# CD_Power_supply.net
KiCad netlist of a schematic drawn in EasyEDA Pro
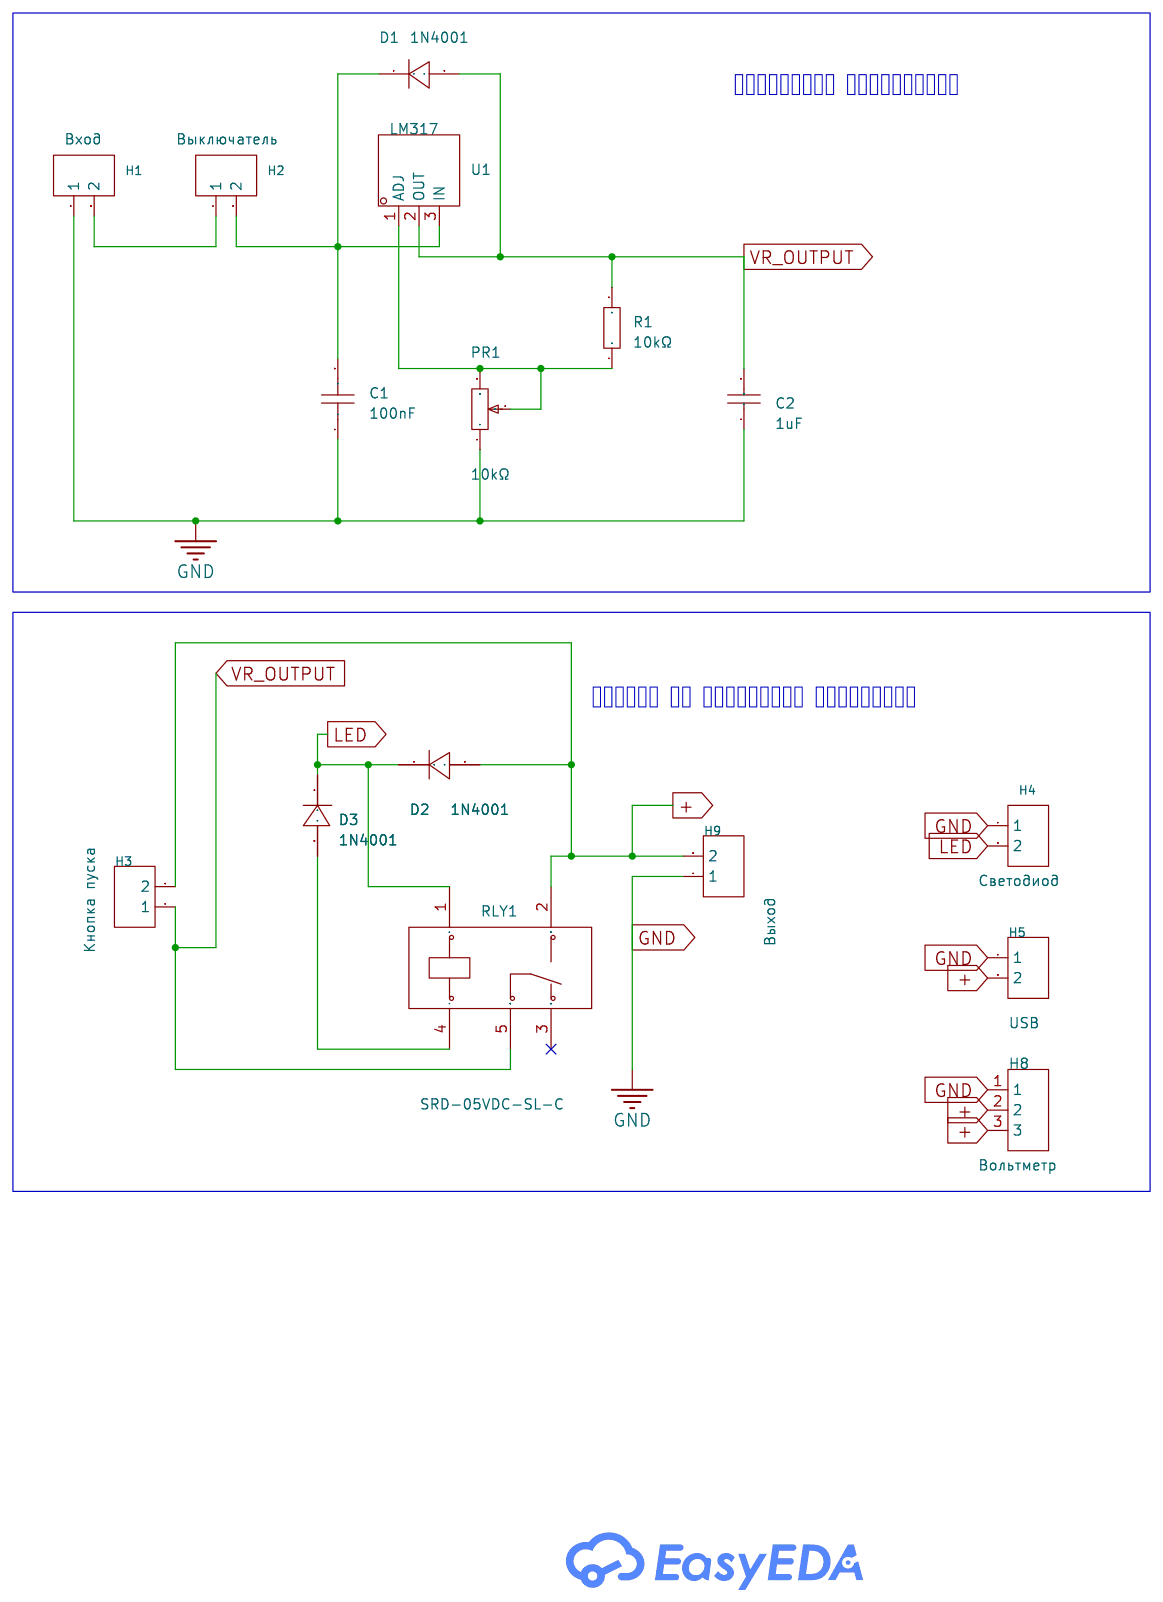
[diagram p0: schematic sheet]

(export (version "E")
  (design (tool "Eeschema 10.0.6"))
  (components
    (comp (ref "C1")
      (value "100nF")
      (footprint "easyedapro:CAP-TH_L8.5-W5.0-P5.00-D1.2")
      (fields (field (name "Manufacturer Part") "CT4-0805B104K500F3") (field (name "Manufacturer") "FH(风华)"))
      (libsource (lib "easyedapro") (part "CT4-0805B104K500F3"))
    )
    (comp (ref "C2")
      (value "1uF")
      (footprint "easyedapro:CAP-TH_L8.5-W5.0-P5.00-D1.2")
      (description "Capacitance:1uF Tolerance:±10% Tolerance:±10% Voltage Rating:50V Temperature Coefficient:X7R")
      (fields (field (name "Manufacturer Part") "CT4-0805B105K500F3") (field (name "Manufacturer") "FH(风华)"))
      (libsource (lib "easyedapro") (part "CT4-0805B105K500F3"))
    )
    (comp (ref "D1")
      (value "1N4001")
      (footprint "easyedapro:DO-41_BD2.4-L4.7-P8.70-D0.9-RD")
      (libsource (lib "easyedapro") (part "1N4001"))
    )
    (comp (ref "D2")
      (value "1N4001")
      (footprint "easyedapro:DO-41_BD2.4-L4.7-P8.70-D0.9-RD")
      (libsource (lib "easyedapro") (part "1N4001"))
    )
    (comp (ref "D3")
      (value "1N4001")
      (footprint "easyedapro:DO-41_BD2.4-L4.7-P8.70-D0.9-RD")
      (libsource (lib "easyedapro") (part "1N4001"))
    )
    (comp (ref "H1")
      (value "Вход")
      (footprint "easyedapro:HDR-TH_2P-P2.54-V-F")
      (libsource (lib "easyedapro") (part "Header-Female-2.54_1x2"))
    )
    (comp (ref "H2")
      (value "Выключатель")
      (footprint "easyedapro:HDR-TH_2P-P2.54-V-F")
      (libsource (lib "easyedapro") (part "Header-Female-2.54_1x2"))
    )
    (comp (ref "H3")
      (value "Кнопка пуска")
      (footprint "easyedapro:HDR-TH_2P-P2.54-V-F")
      (libsource (lib "easyedapro") (part "Header-Female-2.54_1x2"))
    )
    (comp (ref "H4")
      (value "Светодиод")
      (footprint "easyedapro:HDR-TH_2P-P2.54-V-F")
      (libsource (lib "easyedapro") (part "Header-Female-2.54_1x2"))
    )
    (comp (ref "H5")
      (value "USB")
      (footprint "easyedapro:HDR-TH_2P-P2.54-V-F")
      (libsource (lib "easyedapro") (part "Header-Female-2.54_1x2"))
    )
    (comp (ref "H8")
      (value "Вольтметр")
      (footprint "easyedapro:HDR-TH_3P-P2.54-V-F")
      (libsource (lib "easyedapro") (part "PM254V-11-03-H85"))
    )
    (comp (ref "H9")
      (value "Выход")
      (footprint "easyedapro:HDR-TH_2P-P2.54-V-F")
      (libsource (lib "easyedapro") (part "Header-Female-2.54_1x2"))
    )
    (comp (ref "PR1")
      (value "10kΩ")
      (footprint "easyedapro:RES-ADJ-TH_3P-L10.0-W10.0-P2.50-L")
      (libsource (lib "easyedapro") (part "3386P-1-103LF"))
    )
    (comp (ref "R1")
      (value "10kΩ")
      (footprint "easyedapro:R_AXIAL-0.4")
      (libsource (lib "easyedapro") (part "Res"))
    )
    (comp (ref "RLY1")
      (value "SRD-05VDC-SL-C")
      (footprint "easyedapro:RELAY-TH_SRD-XXVDC-XL-C")
      (fields (field (name "Manufacturer") "松乐"))
      (libsource (lib "easyedapro") (part "SRD-05VDC-SL-C"))
    )
    (comp (ref "U1")
      (value "LM317")
      (footprint "easyedapro:TO-220-3_L10.0-W4.5-P2.54-L")
      (fields (field (name "Manufacturer") "BLUE ROCKET(蓝箭)"))
      (libsource (lib "easyedapro") (part "LM317_C358377"))
    )
  )
  (nets
    (net (code "1") (name "+") (class "Default")
      (node (ref "D2") (pin "2") (pinfunction "A_2") (pintype "unspecified"))
      (node (ref "H3") (pin "2") (pinfunction "2_2") (pintype "input"))
      (node (ref "H5") (pin "2") (pinfunction "2_2") (pintype "input"))
      (node (ref "H8") (pin "2") (pinfunction "2_2") (pintype "unspecified"))
      (node (ref "H8") (pin "3") (pinfunction "3_3") (pintype "unspecified"))
      (node (ref "H9") (pin "2") (pinfunction "2_2") (pintype "input"))
      (node (ref "RLY1") (pin "2") (pinfunction "2_2") (pintype "input"))
    )
    (net (code "2") (name "GND") (class "Default")
      (node (ref "C1") (pin "1") (pinfunction "1_1") (pintype "unspecified"))
      (node (ref "C2") (pin "1") (pinfunction "1_1") (pintype "input"))
      (node (ref "H1") (pin "1") (pinfunction "1_1") (pintype "input"))
      (node (ref "H4") (pin "1") (pinfunction "1_1") (pintype "input"))
      (node (ref "H5") (pin "1") (pinfunction "1_1") (pintype "input"))
      (node (ref "H8") (pin "1") (pinfunction "1_1") (pintype "unspecified"))
      (node (ref "H9") (pin "1") (pinfunction "1_1") (pintype "input"))
      (node (ref "PR1") (pin "1") (pinfunction "1_1") (pintype "input"))
    )
    (net (code "3") (name "LED") (class "Default")
      (node (ref "D2") (pin "1") (pinfunction "K_1") (pintype "unspecified"))
      (node (ref "D3") (pin "1") (pinfunction "K_1") (pintype "unspecified"))
      (node (ref "H4") (pin "2") (pinfunction "2_2") (pintype "input"))
      (node (ref "RLY1") (pin "1") (pinfunction "1_1") (pintype "input"))
    )
    (net (code "4") (name "Net-(D1-K)") (class "Default")
      (node (ref "C1") (pin "2") (pinfunction "2_2") (pintype "unspecified"))
      (node (ref "D1") (pin "1") (pinfunction "K_1") (pintype "unspecified"))
      (node (ref "H2") (pin "2") (pinfunction "2_2") (pintype "input"))
      (node (ref "U1") (pin "3") (pinfunction "IN_3") (pintype "input"))
    )
    (net (code "5") (name "Net-(D3-A)") (class "Default")
      (node (ref "D3") (pin "2") (pinfunction "A_2") (pintype "unspecified"))
      (node (ref "RLY1") (pin "4") (pinfunction "4_4") (pintype "input"))
    )
    (net (code "6") (name "Net-(H1-Pad2)") (class "Default")
      (node (ref "H1") (pin "2") (pinfunction "2_2") (pintype "input"))
      (node (ref "H2") (pin "1") (pinfunction "1_1") (pintype "input"))
    )
    (net (code "7") (name "Net-(U1-ADJ)") (class "Default")
      (node (ref "PR1") (pin "2") (pinfunction "2_2") (pintype "input"))
      (node (ref "PR1") (pin "3") (pinfunction "3_3") (pintype "input"))
      (node (ref "R1") (pin "1") (pinfunction "1_1") (pintype "input"))
      (node (ref "U1") (pin "1") (pinfunction "ADJ_1") (pintype "input"))
    )
    (net (code "8") (name "VR_OUTPUT") (class "Default")
      (node (ref "C2") (pin "2") (pinfunction "2_2") (pintype "input"))
      (node (ref "D1") (pin "2") (pinfunction "A_2") (pintype "unspecified"))
      (node (ref "H3") (pin "1") (pinfunction "1_1") (pintype "input"))
      (node (ref "R1") (pin "2") (pinfunction "2_2") (pintype "input"))
      (node (ref "RLY1") (pin "5") (pinfunction "5_5") (pintype "input"))
      (node (ref "U1") (pin "2") (pinfunction "OUT_2") (pintype "input"))
    )
    (net (code "9") (name "unconnected-(RLY1-Pad3)") (class "Default")
      (node (ref "RLY1") (pin "3") (pinfunction "3_3") (pintype "input+no_connect"))
    )
  )
)
